# vs1003.net
KiCad netlist of a schematic drawn in Altium Designer
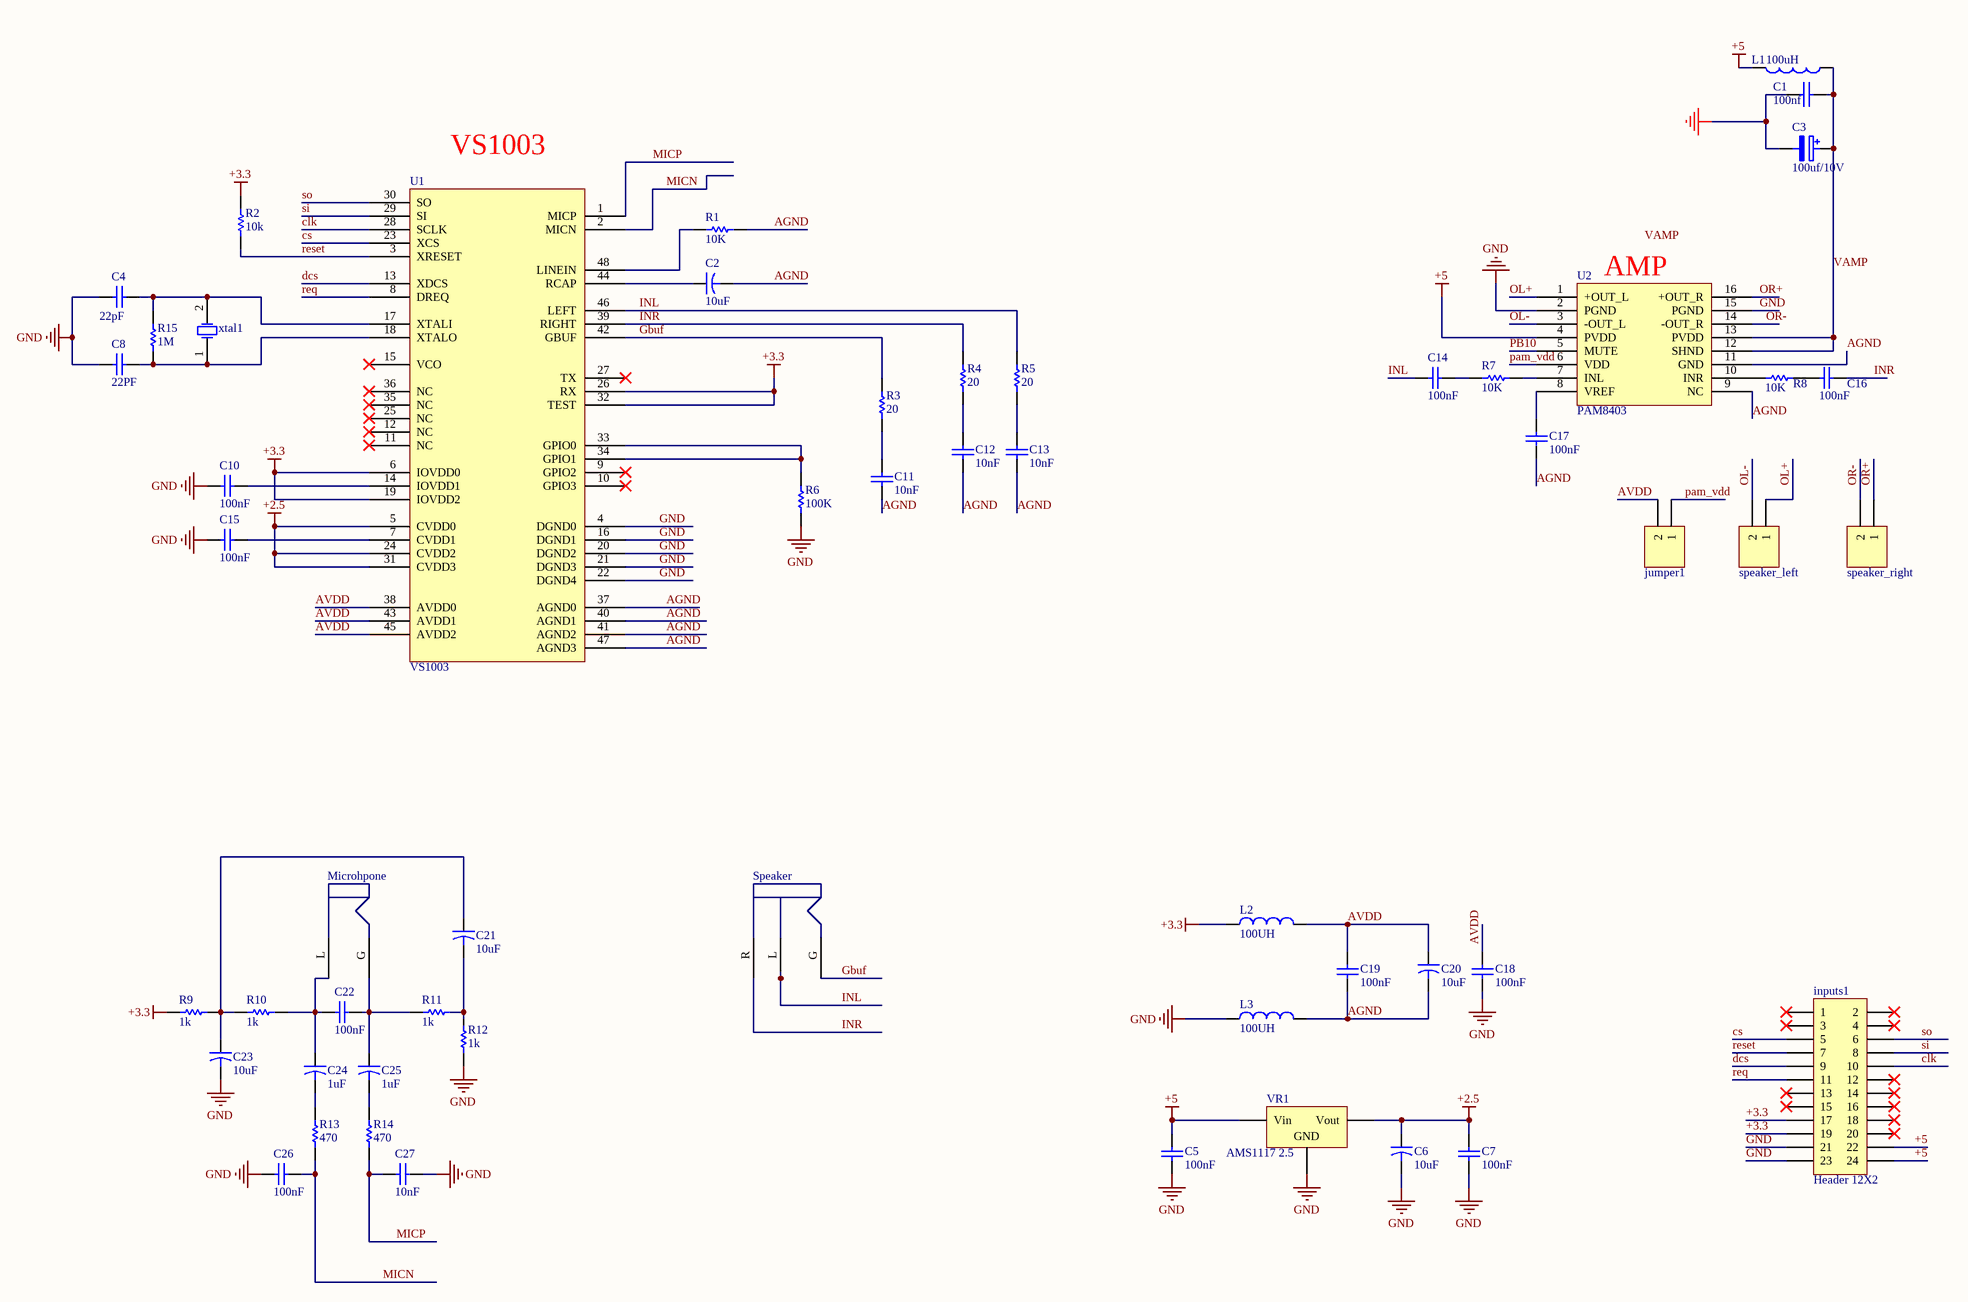
[diagram p0: vs1003.SchDoc]

(export (version "E")
  (design (tool "Eeschema 10.0.6"))
  (components
    (comp (ref "C1") (value "100nf") (footprint "1206") (libsource (lib "*") (part "CAP")))
    (comp (ref "C2")
      (value "10uF")
      (footprint "1206")
      (description "Capacitor")
      (fields (field (name "PUBLISHER") "Altium Limited"))
      (libsource (lib "Miscellaneous Devices") (part "Cap2"))
    )
    (comp (ref "C3")
      (value "100uf/10V")
      (footprint "SMD -D")
      (description "Electrolytic Capacitor")
      (libsource (lib "*") (part "ELECTRO2"))
    )
    (comp (ref "C4")
      (value "22pF")
      (footprint "1206")
      (description "Capacitor")
      (fields (field (name "Comment") "Cap") (field (name "PUBLISHER") "Altium Limited"))
      (libsource (lib "Miscellaneous Devices") (part "Cap"))
    )
    (comp (ref "C5")
      (value "100nF")
      (footprint "1206")
      (description "Capacitor (Semiconductor SIM Model)")
      (fields (field (name "PUBLISHER") "Altium Limited"))
      (libsource (lib "Miscellaneous Devices") (part "Cap Semi"))
    )
    (comp (ref "C6")
      (value "10uF")
      (footprint "1206")
      (description "Capacitor")
      (fields (field (name "PUBLISHER") "Altium Limited"))
      (libsource (lib "Miscellaneous Devices") (part "Cap2"))
    )
    (comp (ref "C7")
      (value "100nF")
      (footprint "1206")
      (description "Capacitor (Semiconductor SIM Model)")
      (fields (field (name "PUBLISHER") "Altium Limited"))
      (libsource (lib "Miscellaneous Devices") (part "Cap Semi"))
    )
    (comp (ref "C8")
      (value "22PF")
      (footprint "1206")
      (description "Capacitor")
      (fields (field (name "PUBLISHER") "Altium Limited"))
      (libsource (lib "Miscellaneous Devices") (part "Cap"))
    )
    (comp (ref "C10")
      (value "100nF")
      (footprint "1206")
      (description "Capacitor (Semiconductor SIM Model)")
      (fields (field (name "PUBLISHER") "Altium Limited"))
      (libsource (lib "Miscellaneous Devices") (part "Cap Semi"))
    )
    (comp (ref "C11")
      (value "10nF")
      (footprint "1206")
      (description "Capacitor (Semiconductor SIM Model)")
      (fields (field (name "PUBLISHER") "Altium Limited"))
      (libsource (lib "Miscellaneous Devices") (part "Cap Semi"))
    )
    (comp (ref "C12")
      (value "10nF")
      (footprint "1206")
      (description "Capacitor (Semiconductor SIM Model)")
      (fields (field (name "PUBLISHER") "Altium Limited"))
      (libsource (lib "Miscellaneous Devices") (part "Cap Semi"))
    )
    (comp (ref "C13")
      (value "10nF")
      (footprint "1206")
      (description "Capacitor (Semiconductor SIM Model)")
      (fields (field (name "PUBLISHER") "Altium Limited"))
      (libsource (lib "Miscellaneous Devices") (part "Cap Semi"))
    )
    (comp (ref "C14")
      (value "100nF")
      (footprint "1206")
      (description "Capacitor (Semiconductor SIM Model)")
      (fields (field (name "PUBLISHER") "Altium Limited"))
      (libsource (lib "Miscellaneous Devices") (part "Cap Semi"))
    )
    (comp (ref "C15")
      (value "100nF")
      (footprint "1206")
      (description "Capacitor (Semiconductor SIM Model)")
      (fields (field (name "PUBLISHER") "Altium Limited"))
      (libsource (lib "Miscellaneous Devices") (part "Cap Semi"))
    )
    (comp (ref "C16")
      (value "100nF")
      (footprint "1206")
      (description "Capacitor (Semiconductor SIM Model)")
      (fields (field (name "PUBLISHER") "Altium Limited"))
      (libsource (lib "Miscellaneous Devices") (part "Cap Semi"))
    )
    (comp (ref "C17")
      (value "100nF")
      (footprint "1206")
      (description "Capacitor (Semiconductor SIM Model)")
      (fields (field (name "PUBLISHER") "Altium Limited"))
      (libsource (lib "Miscellaneous Devices") (part "Cap Semi"))
    )
    (comp (ref "C18")
      (value "100nF")
      (footprint "1206")
      (description "Capacitor (Semiconductor SIM Model)")
      (fields (field (name "PUBLISHER") "Altium Limited"))
      (libsource (lib "Miscellaneous Devices") (part "Cap Semi"))
    )
    (comp (ref "C19")
      (value "100nF")
      (footprint "1206")
      (description "Capacitor (Semiconductor SIM Model)")
      (fields (field (name "PUBLISHER") "Altium Limited"))
      (libsource (lib "Miscellaneous Devices") (part "Cap Semi"))
    )
    (comp (ref "C20")
      (value "10uF")
      (footprint "1206")
      (description "Capacitor")
      (fields (field (name "PUBLISHER") "Altium Limited"))
      (libsource (lib "Miscellaneous Devices") (part "Cap2"))
    )
    (comp (ref "C21")
      (value "10uF")
      (footprint "1206")
      (description "Capacitor")
      (fields (field (name "PUBLISHER") "Altium Limited"))
      (libsource (lib "Miscellaneous Devices") (part "Cap2"))
    )
    (comp (ref "C22")
      (value "100nF")
      (footprint "1206")
      (description "Capacitor (Semiconductor SIM Model)")
      (fields (field (name "PUBLISHER") "Altium Limited"))
      (libsource (lib "Miscellaneous Devices") (part "Cap Semi"))
    )
    (comp (ref "C23")
      (value "10uF")
      (footprint "1206")
      (description "Capacitor")
      (fields (field (name "PUBLISHER") "Altium Limited"))
      (libsource (lib "Miscellaneous Devices") (part "Cap2"))
    )
    (comp (ref "C24")
      (value "1uF")
      (footprint "1206")
      (description "Capacitor")
      (fields (field (name "PUBLISHER") "Altium Limited"))
      (libsource (lib "Miscellaneous Devices") (part "Cap2"))
    )
    (comp (ref "C25")
      (value "1uF")
      (footprint "1206")
      (description "Capacitor")
      (fields (field (name "PUBLISHER") "Altium Limited"))
      (libsource (lib "Miscellaneous Devices") (part "Cap2"))
    )
    (comp (ref "C26")
      (value "100nF")
      (footprint "1206")
      (description "Capacitor (Semiconductor SIM Model)")
      (fields (field (name "PUBLISHER") "Altium Limited"))
      (libsource (lib "Miscellaneous Devices") (part "Cap Semi"))
    )
    (comp (ref "C27")
      (value "10nF")
      (footprint "1206")
      (description "Capacitor (Semiconductor SIM Model)")
      (fields (field (name "PUBLISHER") "Altium Limited"))
      (libsource (lib "Miscellaneous Devices") (part "Cap Semi"))
    )
    (comp (ref "inputs1")
      (value "Header 12X2")
      (footprint "HDR2X12")
      (description "Header, 12-Pin, Dual row")
      (fields (field (name "PUBLISHER") "Altium Limited"))
      (libsource (lib "Miscellaneous Connectors") (part "Header 12X2"))
    )
    (comp (ref "jumper1")
      (value "Header 2")
      (footprint "HDR1X2")
      (description "Header, 2-Pin")
      (fields (field (name "PUBLISHER") "Altium Limited"))
      (libsource (lib "Miscellaneous Connectors") (part "Header 2"))
    )
    (comp (ref "L1") (value "100uH") (footprint "1206") (libsource (lib "*") (part "INDUCTOR1")))
    (comp (ref "L2")
      (value "100UH")
      (footprint "1206")
      (description "Inductor")
      (fields (field (name "PUBLISHER") "Altium Limited"))
      (libsource (lib "Miscellaneous Devices") (part "Inductor"))
    )
    (comp (ref "L3")
      (value "100UH")
      (footprint "1206")
      (description "Inductor")
      (fields (field (name "PUBLISHER") "Altium Limited"))
      (libsource (lib "Miscellaneous Devices") (part "Inductor"))
    )
    (comp (ref "Microhpone")
      (value "Microhpone")
      (footprint "SPEAKER")
      (libsource (lib "myPhonejack") (part "myPhoneJack"))
    )
    (comp (ref "R1")
      (value "10K")
      (footprint "1206")
      (description "Semiconductor Resistor")
      (fields (field (name "PUBLISHER") "Altium Limited"))
      (libsource (lib "Miscellaneous Devices") (part "Res Semi"))
    )
    (comp (ref "R2")
      (value "10k")
      (footprint "1206")
      (description "Semiconductor Resistor")
      (fields (field (name "PUBLISHER") "Altium Limited"))
      (libsource (lib "Miscellaneous Devices") (part "Res Semi"))
    )
    (comp (ref "R3")
      (value "20")
      (footprint "1206")
      (description "Semiconductor Resistor")
      (fields (field (name "PUBLISHER") "Altium Limited"))
      (libsource (lib "Miscellaneous Devices") (part "Res Semi"))
    )
    (comp (ref "R4")
      (value "20")
      (footprint "1206")
      (description "Semiconductor Resistor")
      (fields (field (name "PUBLISHER") "Altium Limited"))
      (libsource (lib "Miscellaneous Devices") (part "Res Semi"))
    )
    (comp (ref "R5")
      (value "20")
      (footprint "1206")
      (description "Semiconductor Resistor")
      (fields (field (name "PUBLISHER") "Altium Limited"))
      (libsource (lib "Miscellaneous Devices") (part "Res Semi"))
    )
    (comp (ref "R6")
      (value "100K")
      (footprint "1206")
      (description "Semiconductor Resistor")
      (fields (field (name "PUBLISHER") "Altium Limited"))
      (libsource (lib "Miscellaneous Devices") (part "Res Semi"))
    )
    (comp (ref "R7")
      (value "10K")
      (footprint "1206")
      (description "Semiconductor Resistor")
      (fields (field (name "PUBLISHER") "Altium Limited"))
      (libsource (lib "Miscellaneous Devices") (part "Res Semi"))
    )
    (comp (ref "R8")
      (value "10K")
      (footprint "1206")
      (description "Semiconductor Resistor")
      (fields (field (name "PUBLISHER") "Altium Limited"))
      (libsource (lib "Miscellaneous Devices") (part "Res Semi"))
    )
    (comp (ref "R9")
      (value "1k")
      (footprint "1206")
      (description "Semiconductor Resistor")
      (fields (field (name "PUBLISHER") "Altium Limited"))
      (libsource (lib "Miscellaneous Devices") (part "Res Semi"))
    )
    (comp (ref "R10")
      (value "1k")
      (footprint "1206")
      (description "Semiconductor Resistor")
      (fields (field (name "PUBLISHER") "Altium Limited"))
      (libsource (lib "Miscellaneous Devices") (part "Res Semi"))
    )
    (comp (ref "R11")
      (value "1k")
      (footprint "1206")
      (description "Semiconductor Resistor")
      (fields (field (name "PUBLISHER") "Altium Limited"))
      (libsource (lib "Miscellaneous Devices") (part "Res Semi"))
    )
    (comp (ref "R12")
      (value "1k")
      (footprint "1206")
      (description "Semiconductor Resistor")
      (fields (field (name "PUBLISHER") "Altium Limited"))
      (libsource (lib "Miscellaneous Devices") (part "Res Semi"))
    )
    (comp (ref "R13")
      (value "470")
      (footprint "1206")
      (description "Semiconductor Resistor")
      (fields (field (name "PUBLISHER") "Altium Limited"))
      (libsource (lib "Miscellaneous Devices") (part "Res Semi"))
    )
    (comp (ref "R14")
      (value "470")
      (footprint "1206")
      (description "Semiconductor Resistor")
      (fields (field (name "PUBLISHER") "Altium Limited"))
      (libsource (lib "Miscellaneous Devices") (part "Res Semi"))
    )
    (comp (ref "R15")
      (value "1M")
      (footprint "1206")
      (description "Semiconductor Resistor")
      (fields (field (name "PUBLISHER") "Altium Limited"))
      (libsource (lib "Miscellaneous Devices") (part "Res Semi"))
    )
    (comp (ref "Speaker")
      (value "Stereo Speaker")
      (footprint "SPEAKER")
      (libsource (lib "myPhonejack") (part "Stereo Speaker"))
    )
    (comp (ref "speaker_left")
      (value "Header 2")
      (footprint "HDR1X2")
      (description "Header, 2-Pin")
      (fields (field (name "PUBLISHER") "Altium Limited"))
      (libsource (lib "Miscellaneous Connectors") (part "Header 2"))
    )
    (comp (ref "speaker_right")
      (value "Header 5")
      (footprint "HDR1X2")
      (description "Header, 2-Pin")
      (fields (field (name "PUBLISHER") "Altium Limited"))
      (libsource (lib "Miscellaneous Connectors") (part "Header 2"))
    )
    (comp (ref "U1") (value "VS1003") (footprint "TQFP48_M2") (libsource (lib "Schlib1") (part "VS1003")))
    (comp (ref "U2") (value "PAM8403") (footprint "751B-05_N") (libsource (lib "Schlib1") (part "PAM8403")))
    (comp (ref "VR1")
      (value "AMS1117 2.5")
      (footprint "Regolator")
      (description "Voltage Regulator")
      (fields (field (name "PUBLISHER") "Altium Limited"))
      (libsource (lib "Miscellaneous Devices") (part "Volt Reg"))
    )
    (comp (ref "xtal1")
      (value "XTAL")
      (footprint "XTAL3")
      (description "Crystal Oscillator")
      (fields (field (name "PUBLISHER") "Altium Limited"))
      (libsource (lib "Miscellaneous Devices") (part "XTAL"))
    )
  )
  (nets
    (net (code "1") (name "+2.5") (class "Default")
      (node (ref "C6") (pin "1") (pinfunction "1_1") (pintype "passive"))
      (node (ref "C7") (pin "2") (pinfunction "2_2") (pintype "passive"))
      (node (ref "U1") (pin "24") (pinfunction "CVDD2_24") (pintype "passive"))
      (node (ref "U1") (pin "31") (pinfunction "CVDD3_31") (pintype "passive"))
      (node (ref "U1") (pin "5") (pinfunction "CVDD0_5") (pintype "passive"))
      (node (ref "VR1") (pin "3") (pinfunction "Vout_3") (pintype "passive"))
    )
    (net (code "2") (name "+3.3") (class "Default")
      (node (ref "L2") (pin "1") (pinfunction "1_1") (pintype "passive"))
      (node (ref "R2") (pin "1") (pinfunction "1_1") (pintype "passive"))
      (node (ref "R9") (pin "1") (pinfunction "1_1") (pintype "passive"))
      (node (ref "U1") (pin "19") (pinfunction "IOVDD2_19") (pintype "passive"))
      (node (ref "U1") (pin "26") (pinfunction "RX_26") (pintype "passive"))
      (node (ref "U1") (pin "32") (pinfunction "TEST_32") (pintype "passive"))
      (node (ref "U1") (pin "6") (pinfunction "IOVDD0_6") (pintype "passive"))
      (node (ref "inputs1") (pin "17") (pinfunction "17_17") (pintype "passive"))
      (node (ref "inputs1") (pin "19") (pinfunction "19_19") (pintype "passive"))
    )
    (net (code "3") (name "+5") (class "Default")
      (node (ref "C5") (pin "2") (pinfunction "2_2") (pintype "passive"))
      (node (ref "L1") (pin "1") (pintype "passive"))
      (node (ref "U2") (pin "4") (pinfunction "PVDD_4") (pintype "passive"))
      (node (ref "VR1") (pin "1") (pinfunction "Vin_1") (pintype "passive"))
      (node (ref "inputs1") (pin "22") (pinfunction "22_22") (pintype "passive"))
      (node (ref "inputs1") (pin "24") (pinfunction "24_24") (pintype "passive"))
    )
    (net (code "4") (name "/AGND") (class "Default")
      (node (ref "C11") (pin "2") (pinfunction "2_2") (pintype "passive"))
      (node (ref "C12") (pin "2") (pinfunction "2_2") (pintype "passive"))
      (node (ref "C13") (pin "2") (pinfunction "2_2") (pintype "passive"))
      (node (ref "C17") (pin "1") (pinfunction "1_1") (pintype "passive"))
      (node (ref "C19") (pin "2") (pinfunction "2_2") (pintype "passive"))
      (node (ref "C2") (pin "2") (pinfunction "2_2") (pintype "passive"))
      (node (ref "C20") (pin "2") (pinfunction "2_2") (pintype "passive"))
      (node (ref "L3") (pin "2") (pinfunction "2_2") (pintype "passive"))
      (node (ref "R1") (pin "1") (pinfunction "1_1") (pintype "passive"))
      (node (ref "U1") (pin "37") (pinfunction "AGND0_37") (pintype "passive"))
      (node (ref "U1") (pin "40") (pinfunction "AGND1_40") (pintype "passive"))
      (node (ref "U1") (pin "41") (pinfunction "AGND2_41") (pintype "passive"))
      (node (ref "U1") (pin "47") (pinfunction "AGND3_47") (pintype "passive"))
      (node (ref "U2") (pin "11") (pinfunction "GND_11") (pintype "passive"))
      (node (ref "U2") (pin "9") (pinfunction "NC_9") (pintype "passive"))
    )
    (net (code "5") (name "/AVDD") (class "Default")
      (node (ref "C18") (pin "1") (pinfunction "1_1") (pintype "passive"))
      (node (ref "C19") (pin "1") (pinfunction "1_1") (pintype "passive"))
      (node (ref "C20") (pin "1") (pinfunction "1_1") (pintype "passive"))
      (node (ref "L2") (pin "2") (pinfunction "2_2") (pintype "passive"))
      (node (ref "U1") (pin "38") (pinfunction "AVDD0_38") (pintype "passive"))
      (node (ref "U1") (pin "43") (pinfunction "AVDD1_43") (pintype "passive"))
      (node (ref "U1") (pin "45") (pinfunction "AVDD2_45") (pintype "passive"))
      (node (ref "jumper1") (pin "2") (pinfunction "2_2") (pintype "passive"))
    )
    (net (code "6") (name "/Gbuf") (class "Default")
      (node (ref "R3") (pin "2") (pinfunction "2_2") (pintype "passive"))
      (node (ref "Speaker") (pin "G") (pinfunction "G_G") (pintype "passive"))
      (node (ref "U1") (pin "42") (pinfunction "GBUF_42") (pintype "passive"))
    )
    (net (code "7") (name "/INL") (class "Default")
      (node (ref "C14") (pin "1") (pinfunction "1_1") (pintype "passive"))
      (node (ref "R5") (pin "1") (pinfunction "1_1") (pintype "passive"))
      (node (ref "Speaker") (pin "L") (pinfunction "L_L") (pintype "passive"))
      (node (ref "U1") (pin "46") (pinfunction "LEFT_46") (pintype "passive"))
    )
    (net (code "8") (name "/INR") (class "Default")
      (node (ref "C16") (pin "2") (pinfunction "2_2") (pintype "passive"))
      (node (ref "R4") (pin "1") (pinfunction "1_1") (pintype "passive"))
      (node (ref "Speaker") (pin "R") (pinfunction "R_R") (pintype "passive"))
      (node (ref "U1") (pin "39") (pinfunction "RIGHT_39") (pintype "passive"))
    )
    (net (code "9") (name "/MICN") (class "Default")
      (node (ref "C26") (pin "2") (pinfunction "2_2") (pintype "passive"))
      (node (ref "R13") (pin "1") (pinfunction "1_1") (pintype "passive"))
      (node (ref "U1") (pin "2") (pinfunction "MICN_2") (pintype "passive"))
    )
    (net (code "10") (name "/MICP") (class "Default")
      (node (ref "C27") (pin "1") (pinfunction "1_1") (pintype "passive"))
      (node (ref "R14") (pin "1") (pinfunction "1_1") (pintype "passive"))
      (node (ref "U1") (pin "1") (pinfunction "MICP_1") (pintype "passive"))
    )
    (net (code "11") (name "/OL+") (class "Default")
      (node (ref "U2") (pin "1") (pinfunction "+OUT_L_1") (pintype "passive"))
      (node (ref "speaker_left") (pin "1") (pinfunction "1_1") (pintype "passive"))
    )
    (net (code "12") (name "/OL-") (class "Default")
      (node (ref "U2") (pin "3") (pinfunction "-OUT_L_3") (pintype "passive"))
      (node (ref "speaker_left") (pin "2") (pinfunction "2_2") (pintype "passive"))
    )
    (net (code "13") (name "/OR+") (class "Default")
      (node (ref "U2") (pin "16") (pinfunction "+OUT_R_16") (pintype "passive"))
      (node (ref "speaker_right") (pin "1") (pinfunction "1_1") (pintype "passive"))
    )
    (net (code "14") (name "/OR-") (class "Default")
      (node (ref "U2") (pin "14") (pinfunction "-OUT_R_14") (pintype "passive"))
      (node (ref "speaker_right") (pin "2") (pinfunction "2_2") (pintype "passive"))
    )
    (net (code "15") (name "/PB10") (class "Default")
      (node (ref "U2") (pin "5") (pinfunction "MUTE_5") (pintype "passive"))
    )
    (net (code "16") (name "/VAMP") (class "Default")
      (node (ref "C1") (pin "1") (pintype "passive"))
      (node (ref "C3") (pin "1") (pinfunction "1_1") (pintype "passive"))
      (node (ref "L1") (pin "2") (pintype "passive"))
      (node (ref "U2") (pin "12") (pinfunction "SHND_12") (pintype "passive"))
      (node (ref "U2") (pin "13") (pinfunction "PVDD_13") (pintype "passive"))
    )
    (net (code "17") (name "/clk") (class "Default")
      (node (ref "U1") (pin "28") (pinfunction "SCLK_28") (pintype "passive"))
      (node (ref "inputs1") (pin "10") (pinfunction "10_10") (pintype "passive"))
    )
    (net (code "18") (name "/cs") (class "Default")
      (node (ref "U1") (pin "23") (pinfunction "XCS_23") (pintype "passive"))
      (node (ref "inputs1") (pin "5") (pinfunction "5_5") (pintype "passive"))
    )
    (net (code "19") (name "/dcs") (class "Default")
      (node (ref "U1") (pin "13") (pinfunction "XDCS_13") (pintype "passive"))
      (node (ref "inputs1") (pin "9") (pinfunction "9_9") (pintype "passive"))
    )
    (net (code "20") (name "/pam_vdd") (class "Default")
      (node (ref "U2") (pin "6") (pinfunction "VDD_6") (pintype "passive"))
      (node (ref "jumper1") (pin "1") (pinfunction "1_1") (pintype "passive"))
    )
    (net (code "21") (name "/req") (class "Default")
      (node (ref "U1") (pin "8") (pinfunction "DREQ_8") (pintype "passive"))
      (node (ref "inputs1") (pin "11") (pinfunction "11_11") (pintype "passive"))
    )
    (net (code "22") (name "/reset") (class "Default")
      (node (ref "R2") (pin "2") (pinfunction "2_2") (pintype "passive"))
      (node (ref "U1") (pin "3") (pinfunction "XRESET_3") (pintype "passive"))
      (node (ref "inputs1") (pin "7") (pinfunction "7_7") (pintype "passive"))
    )
    (net (code "23") (name "/si") (class "Default")
      (node (ref "U1") (pin "29") (pinfunction "SI_29") (pintype "passive"))
      (node (ref "inputs1") (pin "8") (pinfunction "8_8") (pintype "passive"))
    )
    (net (code "24") (name "/so") (class "Default")
      (node (ref "U1") (pin "30") (pinfunction "SO_30") (pintype "passive"))
      (node (ref "inputs1") (pin "6") (pinfunction "6_6") (pintype "passive"))
    )
    (net (code "25") (name "GND") (class "Default")
      (node (ref "C1") (pin "2") (pintype "passive"))
      (node (ref "C10") (pin "2") (pinfunction "2_2") (pintype "passive"))
      (node (ref "C15") (pin "2") (pinfunction "2_2") (pintype "passive"))
      (node (ref "C18") (pin "2") (pinfunction "2_2") (pintype "passive"))
      (node (ref "C23") (pin "2") (pinfunction "2_2") (pintype "passive"))
      (node (ref "C26") (pin "1") (pinfunction "1_1") (pintype "passive"))
      (node (ref "C27") (pin "2") (pinfunction "2_2") (pintype "passive"))
      (node (ref "C3") (pin "2") (pinfunction "2_2") (pintype "passive"))
      (node (ref "C4") (pin "1") (pinfunction "1_1") (pintype "passive"))
      (node (ref "C5") (pin "1") (pinfunction "1_1") (pintype "passive"))
      (node (ref "C6") (pin "2") (pinfunction "2_2") (pintype "passive"))
      (node (ref "C7") (pin "1") (pinfunction "1_1") (pintype "passive"))
      (node (ref "C8") (pin "1") (pinfunction "1_1") (pintype "passive"))
      (node (ref "L3") (pin "1") (pinfunction "1_1") (pintype "passive"))
      (node (ref "R12") (pin "2") (pinfunction "2_2") (pintype "passive"))
      (node (ref "R6") (pin "1") (pinfunction "1_1") (pintype "passive"))
      (node (ref "U1") (pin "16") (pinfunction "DGND1_16") (pintype "passive"))
      (node (ref "U1") (pin "20") (pinfunction "DGND2_20") (pintype "passive"))
      (node (ref "U1") (pin "21") (pinfunction "DGND3_21") (pintype "passive"))
      (node (ref "U1") (pin "22") (pinfunction "DGND4_22") (pintype "passive"))
      (node (ref "U1") (pin "4") (pinfunction "DGND0_4") (pintype "passive"))
      (node (ref "U2") (pin "15") (pinfunction "PGND_15") (pintype "passive"))
      (node (ref "U2") (pin "2") (pinfunction "PGND_2") (pintype "passive"))
      (node (ref "VR1") (pin "2") (pinfunction "GND_2") (pintype "passive"))
      (node (ref "inputs1") (pin "21") (pinfunction "21_21") (pintype "passive"))
      (node (ref "inputs1") (pin "23") (pinfunction "23_23") (pintype "passive"))
    )
    (net (code "26") (name "Net-(C11-Pad1)") (class "Default")
      (node (ref "C11") (pin "1") (pinfunction "1_1") (pintype "passive"))
      (node (ref "R3") (pin "1") (pinfunction "1_1") (pintype "passive"))
    )
    (net (code "27") (name "Net-(C12-Pad1)") (class "Default")
      (node (ref "C12") (pin "1") (pinfunction "1_1") (pintype "passive"))
      (node (ref "R4") (pin "2") (pinfunction "2_2") (pintype "passive"))
    )
    (net (code "28") (name "Net-(C13-Pad1)") (class "Default")
      (node (ref "C13") (pin "1") (pinfunction "1_1") (pintype "passive"))
      (node (ref "R5") (pin "2") (pinfunction "2_2") (pintype "passive"))
    )
    (net (code "29") (name "Net-(C14-Pad2)") (class "Default")
      (node (ref "C14") (pin "2") (pinfunction "2_2") (pintype "passive"))
      (node (ref "R7") (pin "2") (pinfunction "2_2") (pintype "passive"))
    )
    (net (code "30") (name "Net-(C16-Pad1)") (class "Default")
      (node (ref "C16") (pin "1") (pinfunction "1_1") (pintype "passive"))
      (node (ref "R8") (pin "1") (pinfunction "1_1") (pintype "passive"))
    )
    (net (code "31") (name "Net-(C21-Pad1)") (class "Default")
      (node (ref "C21") (pin "1") (pinfunction "1_1") (pintype "passive"))
      (node (ref "C23") (pin "1") (pinfunction "1_1") (pintype "passive"))
      (node (ref "R10") (pin "1") (pinfunction "1_1") (pintype "passive"))
      (node (ref "R9") (pin "2") (pinfunction "2_2") (pintype "passive"))
    )
    (net (code "32") (name "Net-(C21-Pad2)") (class "Default")
      (node (ref "C21") (pin "2") (pinfunction "2_2") (pintype "passive"))
      (node (ref "R11") (pin "2") (pinfunction "2_2") (pintype "passive"))
      (node (ref "R12") (pin "1") (pinfunction "1_1") (pintype "passive"))
    )
    (net (code "33") (name "Net-(C22-Pad1)") (class "Default")
      (node (ref "C22") (pin "1") (pinfunction "1_1") (pintype "passive"))
      (node (ref "C24") (pin "1") (pinfunction "1_1") (pintype "passive"))
      (node (ref "Microhpone") (pin "L") (pinfunction "L_L") (pintype "passive"))
      (node (ref "R10") (pin "2") (pinfunction "2_2") (pintype "passive"))
    )
    (net (code "34") (name "Net-(C22-Pad2)") (class "Default")
      (node (ref "C22") (pin "2") (pinfunction "2_2") (pintype "passive"))
      (node (ref "C25") (pin "1") (pinfunction "1_1") (pintype "passive"))
      (node (ref "Microhpone") (pin "G") (pinfunction "L_G") (pintype "passive"))
      (node (ref "R11") (pin "1") (pinfunction "1_1") (pintype "passive"))
    )
    (net (code "35") (name "Net-(C24-Pad2)") (class "Default")
      (node (ref "C24") (pin "2") (pinfunction "2_2") (pintype "passive"))
      (node (ref "R13") (pin "2") (pinfunction "2_2") (pintype "passive"))
    )
    (net (code "36") (name "Net-(C25-Pad2)") (class "Default")
      (node (ref "C25") (pin "2") (pinfunction "2_2") (pintype "passive"))
      (node (ref "R14") (pin "2") (pinfunction "2_2") (pintype "passive"))
    )
    (net (code "37") (name "Net-(U1-CVDD1)") (class "Default")
      (node (ref "C15") (pin "1") (pinfunction "1_1") (pintype "passive"))
      (node (ref "U1") (pin "7") (pinfunction "CVDD1_7") (pintype "passive"))
    )
    (net (code "38") (name "Net-(U1-GPIO0)") (class "Default")
      (node (ref "R6") (pin "2") (pinfunction "2_2") (pintype "passive"))
      (node (ref "U1") (pin "33") (pinfunction "GPIO0_33") (pintype "passive"))
      (node (ref "U1") (pin "34") (pinfunction "GPIO1_34") (pintype "passive"))
    )
    (net (code "39") (name "Net-(U1-IOVDD1)") (class "Default")
      (node (ref "C10") (pin "1") (pinfunction "1_1") (pintype "passive"))
      (node (ref "U1") (pin "14") (pinfunction "IOVDD1_14") (pintype "passive"))
    )
    (net (code "40") (name "Net-(U1-LINEIN)") (class "Default")
      (node (ref "R1") (pin "2") (pinfunction "2_2") (pintype "passive"))
      (node (ref "U1") (pin "48") (pinfunction "LINEIN_48") (pintype "passive"))
    )
    (net (code "41") (name "Net-(U1-RCAP)") (class "Default")
      (node (ref "C2") (pin "1") (pinfunction "1_1") (pintype "passive"))
      (node (ref "U1") (pin "44") (pinfunction "RCAP_44") (pintype "passive"))
    )
    (net (code "42") (name "Net-(U1-XTALI)") (class "Default")
      (node (ref "C4") (pin "2") (pinfunction "2_2") (pintype "passive"))
      (node (ref "R15") (pin "1") (pinfunction "1_1") (pintype "passive"))
      (node (ref "U1") (pin "17") (pinfunction "XTALI_17") (pintype "passive"))
      (node (ref "xtal1") (pin "2") (pinfunction "OSC2_2") (pintype "passive"))
    )
    (net (code "43") (name "Net-(U1-XTALO)") (class "Default")
      (node (ref "C8") (pin "2") (pinfunction "2_2") (pintype "passive"))
      (node (ref "R15") (pin "2") (pinfunction "2_2") (pintype "passive"))
      (node (ref "U1") (pin "18") (pinfunction "XTALO_18") (pintype "passive"))
      (node (ref "xtal1") (pin "1") (pinfunction "OSC1_1") (pintype "passive"))
    )
    (net (code "44") (name "Net-(U2-INL)") (class "Default")
      (node (ref "R7") (pin "1") (pinfunction "1_1") (pintype "passive"))
      (node (ref "U2") (pin "7") (pinfunction "INL_7") (pintype "passive"))
    )
    (net (code "45") (name "Net-(U2-INR)") (class "Default")
      (node (ref "R8") (pin "2") (pinfunction "2_2") (pintype "passive"))
      (node (ref "U2") (pin "10") (pinfunction "INR_10") (pintype "passive"))
    )
    (net (code "46") (name "Net-(U2-VREF)") (class "Default")
      (node (ref "C17") (pin "2") (pinfunction "2_2") (pintype "passive"))
      (node (ref "U2") (pin "8") (pinfunction "VREF_8") (pintype "passive"))
    )
    (net (code "47") (name "unconnected-(U1-GPIO2-Pad9)") (class "Default")
      (node (ref "U1") (pin "9") (pinfunction "GPIO2_9") (pintype "passive+no_connect"))
    )
    (net (code "48") (name "unconnected-(U1-GPIO3-Pad10)") (class "Default")
      (node (ref "U1") (pin "10") (pinfunction "GPIO3_10") (pintype "passive+no_connect"))
    )
    (net (code "49") (name "unconnected-(U1-NC-Pad11)") (class "Default")
      (node (ref "U1") (pin "11") (pinfunction "NC_11") (pintype "passive+no_connect"))
    )
    (net (code "50") (name "unconnected-(U1-NC-Pad12)") (class "Default")
      (node (ref "U1") (pin "12") (pinfunction "NC_12") (pintype "passive+no_connect"))
    )
    (net (code "51") (name "unconnected-(U1-NC-Pad25)") (class "Default")
      (node (ref "U1") (pin "25") (pinfunction "NC_25") (pintype "passive+no_connect"))
    )
    (net (code "52") (name "unconnected-(U1-NC-Pad35)") (class "Default")
      (node (ref "U1") (pin "35") (pinfunction "NC_35") (pintype "passive+no_connect"))
    )
    (net (code "53") (name "unconnected-(U1-NC-Pad36)") (class "Default")
      (node (ref "U1") (pin "36") (pinfunction "NC_36") (pintype "passive+no_connect"))
    )
    (net (code "54") (name "unconnected-(U1-TX-Pad27)") (class "Default")
      (node (ref "U1") (pin "27") (pinfunction "TX_27") (pintype "passive+no_connect"))
    )
    (net (code "55") (name "unconnected-(U1-VCO-Pad15)") (class "Default")
      (node (ref "U1") (pin "15") (pinfunction "VCO_15") (pintype "passive+no_connect"))
    )
    (net (code "56") (name "unconnected-(inputs1-Pad1)") (class "Default")
      (node (ref "inputs1") (pin "1") (pinfunction "1_1") (pintype "passive+no_connect"))
    )
    (net (code "57") (name "unconnected-(inputs1-Pad2)") (class "Default")
      (node (ref "inputs1") (pin "2") (pinfunction "2_2") (pintype "passive+no_connect"))
    )
    (net (code "58") (name "unconnected-(inputs1-Pad3)") (class "Default")
      (node (ref "inputs1") (pin "3") (pinfunction "3_3") (pintype "passive+no_connect"))
    )
    (net (code "59") (name "unconnected-(inputs1-Pad4)") (class "Default")
      (node (ref "inputs1") (pin "4") (pinfunction "4_4") (pintype "passive+no_connect"))
    )
    (net (code "60") (name "unconnected-(inputs1-Pad12)") (class "Default")
      (node (ref "inputs1") (pin "12") (pinfunction "12_12") (pintype "passive+no_connect"))
    )
    (net (code "61") (name "unconnected-(inputs1-Pad13)") (class "Default")
      (node (ref "inputs1") (pin "13") (pinfunction "13_13") (pintype "passive+no_connect"))
    )
    (net (code "62") (name "unconnected-(inputs1-Pad14)") (class "Default")
      (node (ref "inputs1") (pin "14") (pinfunction "14_14") (pintype "passive+no_connect"))
    )
    (net (code "63") (name "unconnected-(inputs1-Pad15)") (class "Default")
      (node (ref "inputs1") (pin "15") (pinfunction "15_15") (pintype "passive+no_connect"))
    )
    (net (code "64") (name "unconnected-(inputs1-Pad16)") (class "Default")
      (node (ref "inputs1") (pin "16") (pinfunction "16_16") (pintype "passive+no_connect"))
    )
    (net (code "65") (name "unconnected-(inputs1-Pad18)") (class "Default")
      (node (ref "inputs1") (pin "18") (pinfunction "18_18") (pintype "passive+no_connect"))
    )
    (net (code "66") (name "unconnected-(inputs1-Pad20)") (class "Default")
      (node (ref "inputs1") (pin "20") (pinfunction "20_20") (pintype "passive+no_connect"))
    )
  )
)
